# Raspberry_Pi_Grove_Base_HAT.net
KiCad netlist of a schematic drawn in EAGLE
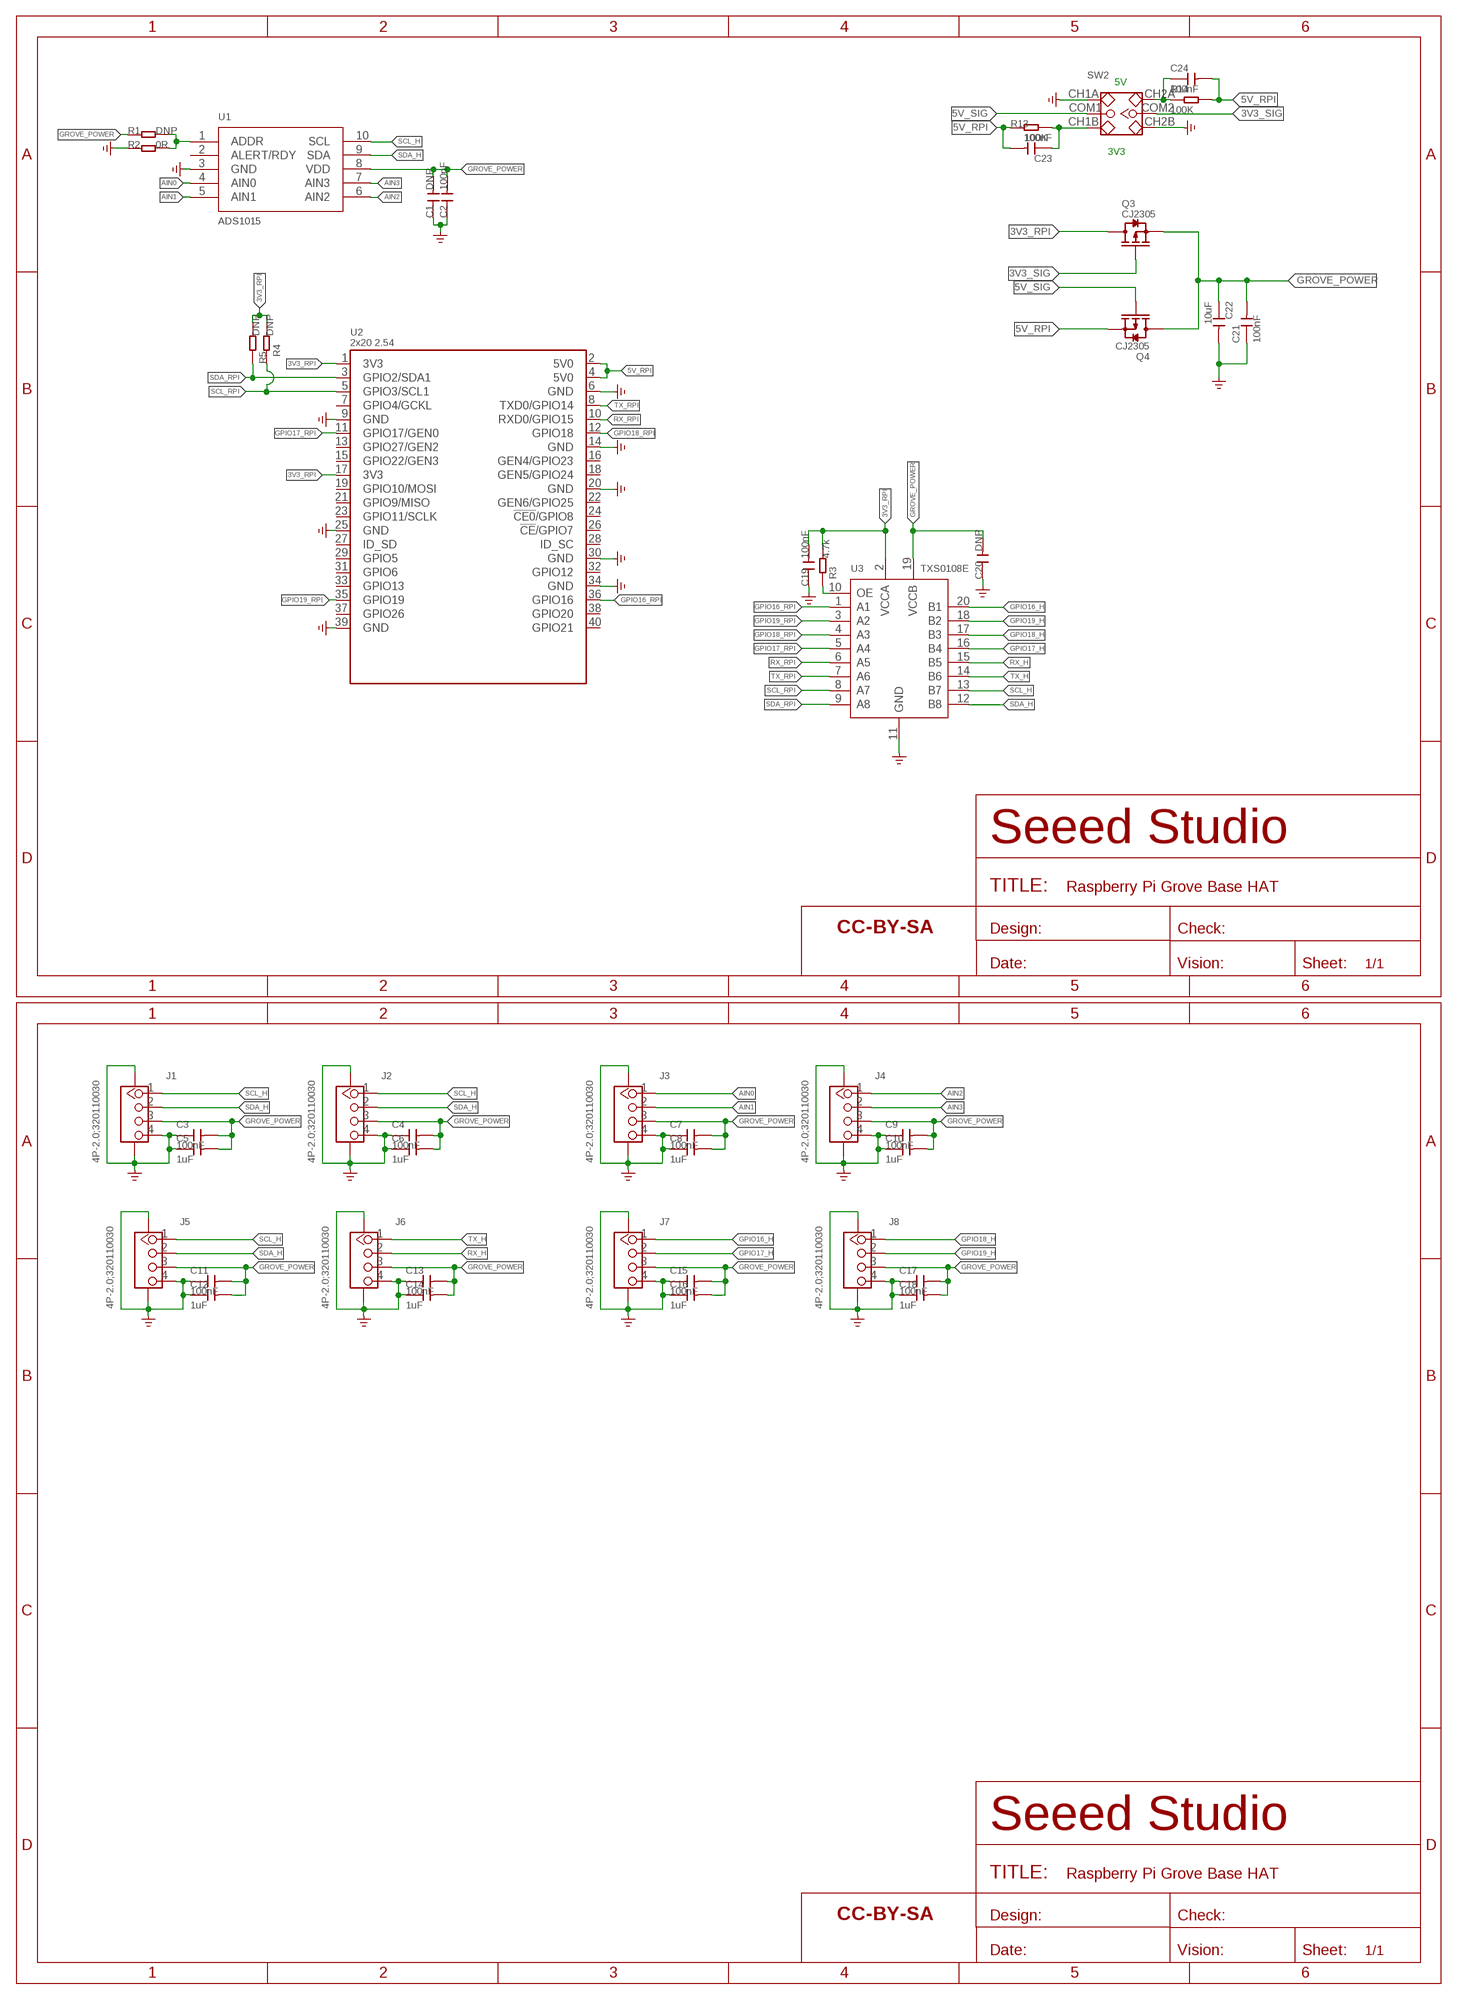
[diagram p0: schematic, sheet 1]

(export (version "E")
  (design (tool "Eeschema 10.0.6"))
  (components
    (comp (ref "C1")
      (value "DNP")
      (footprint "eagle-import:C0603")
      (libsource (lib "eagle-import") (part "CAP-0603"))
    )
    (comp (ref "C2")
      (value "100nF")
      (footprint "eagle-import:C0603")
      (libsource (lib "eagle-import") (part "CAP-0603"))
    )
    (comp (ref "C3")
      (value "100nF")
      (footprint "eagle-import:C0603")
      (libsource (lib "eagle-import") (part "CAP-0603"))
    )
    (comp (ref "C4")
      (value "100nF")
      (footprint "eagle-import:C0603")
      (libsource (lib "eagle-import") (part "CAP-0603"))
    )
    (comp (ref "C5")
      (value "1uF")
      (footprint "eagle-import:C0603")
      (libsource (lib "eagle-import") (part "CAP-0603"))
    )
    (comp (ref "C6")
      (value "1uF")
      (footprint "eagle-import:C0603")
      (libsource (lib "eagle-import") (part "CAP-0603"))
    )
    (comp (ref "C7")
      (value "100nF")
      (footprint "eagle-import:C0603")
      (libsource (lib "eagle-import") (part "CAP-0603"))
    )
    (comp (ref "C8")
      (value "1uF")
      (footprint "eagle-import:C0603")
      (libsource (lib "eagle-import") (part "CAP-0603"))
    )
    (comp (ref "C9")
      (value "100nF")
      (footprint "eagle-import:C0603")
      (libsource (lib "eagle-import") (part "CAP-0603"))
    )
    (comp (ref "C10")
      (value "1uF")
      (footprint "eagle-import:C0603")
      (libsource (lib "eagle-import") (part "CAP-0603"))
    )
    (comp (ref "C11")
      (value "100nF")
      (footprint "eagle-import:C0603")
      (libsource (lib "eagle-import") (part "CAP-0603"))
    )
    (comp (ref "C12")
      (value "1uF")
      (footprint "eagle-import:C0603")
      (libsource (lib "eagle-import") (part "CAP-0603"))
    )
    (comp (ref "C13")
      (value "100nF")
      (footprint "eagle-import:C0603")
      (libsource (lib "eagle-import") (part "CAP-0603"))
    )
    (comp (ref "C14")
      (value "1uF")
      (footprint "eagle-import:C0603")
      (libsource (lib "eagle-import") (part "CAP-0603"))
    )
    (comp (ref "C15")
      (value "100nF")
      (footprint "eagle-import:C0603")
      (libsource (lib "eagle-import") (part "CAP-0603"))
    )
    (comp (ref "C16")
      (value "1uF")
      (footprint "eagle-import:C0603")
      (libsource (lib "eagle-import") (part "CAP-0603"))
    )
    (comp (ref "C17")
      (value "100nF")
      (footprint "eagle-import:C0603")
      (libsource (lib "eagle-import") (part "CAP-0603"))
    )
    (comp (ref "C18")
      (value "1uF")
      (footprint "eagle-import:C0603")
      (libsource (lib "eagle-import") (part "CAP-0603"))
    )
    (comp (ref "C19")
      (value "100nF")
      (footprint "eagle-import:C0603")
      (libsource (lib "eagle-import") (part "CAP-0603"))
    )
    (comp (ref "C20")
      (value "DNP")
      (footprint "eagle-import:C0603")
      (libsource (lib "eagle-import") (part "CAP-0603"))
    )
    (comp (ref "C21")
      (value "100nF")
      (footprint "eagle-import:C0603")
      (libsource (lib "eagle-import") (part "CAP-0603"))
    )
    (comp (ref "C22")
      (value "10uF")
      (footprint "eagle-import:C0603")
      (libsource (lib "eagle-import") (part "CAP-0603"))
    )
    (comp (ref "C23")
      (value "100nF")
      (footprint "eagle-import:C0603")
      (libsource (lib "eagle-import") (part "CAP-0603"))
    )
    (comp (ref "C24")
      (value "100nF")
      (footprint "eagle-import:C0603")
      (libsource (lib "eagle-import") (part "CAP-0603"))
    )
    (comp (ref "FR")
      (value "SEEEDSTUDIO-OPEN-SCH-FRAME")
      (footprint "eagle-import:SEEEDSTUDIO-PCB-FRAME")
      (libsource (lib "eagle-import") (part "SEEEDSTUDIO-OPEN-SCH-FRAME"))
    )
    (comp (ref "FR1")
      (value "SEEEDSTUDIO-OPEN-SCH-FRAME")
      (footprint "eagle-import:SEEEDSTUDIO-PCB-FRAME")
      (libsource (lib "eagle-import") (part "SEEEDSTUDIO-OPEN-SCH-FRAME"))
    )
    (comp (ref "J1")
      (value "4P-2.0;320110030")
      (footprint "eagle-import:HW4-SMD-2.0")
      (libsource (lib "eagle-import") (part "GROVE-CONNECTOR-SMD'DD'"))
    )
    (comp (ref "J2")
      (value "4P-2.0;320110030")
      (footprint "eagle-import:HW4-SMD-2.0")
      (libsource (lib "eagle-import") (part "GROVE-CONNECTOR-SMD'DD'"))
    )
    (comp (ref "J3")
      (value "4P-2.0;320110030")
      (footprint "eagle-import:HW4-SMD-2.0")
      (libsource (lib "eagle-import") (part "GROVE-CONNECTOR-SMD'DD'"))
    )
    (comp (ref "J4")
      (value "4P-2.0;320110030")
      (footprint "eagle-import:HW4-SMD-2.0")
      (libsource (lib "eagle-import") (part "GROVE-CONNECTOR-SMD'DD'"))
    )
    (comp (ref "J5")
      (value "4P-2.0;320110030")
      (footprint "eagle-import:HW4-SMD-2.0")
      (libsource (lib "eagle-import") (part "GROVE-CONNECTOR-SMD'DD'"))
    )
    (comp (ref "J6")
      (value "4P-2.0;320110030")
      (footprint "eagle-import:HW4-SMD-2.0")
      (libsource (lib "eagle-import") (part "GROVE-CONNECTOR-SMD'DD'"))
    )
    (comp (ref "J7")
      (value "4P-2.0;320110030")
      (footprint "eagle-import:HW4-SMD-2.0-90D")
      (libsource (lib "eagle-import") (part "GROVE-CONNECTOR-SMD'90D'"))
    )
    (comp (ref "J8")
      (value "4P-2.0;320110030")
      (footprint "eagle-import:HW4-SMD-2.0-90D")
      (libsource (lib "eagle-import") (part "GROVE-CONNECTOR-SMD'90D'"))
    )
    (comp (ref "Q3")
      (value "CJ2305")
      (footprint "eagle-import:SOT-23")
      (libsource (lib "eagle-import") (part "MOSFET-P'SI2323CDS/SI2305DS{lt}BR{gt}'"))
    )
    (comp (ref "Q4")
      (value "CJ2305")
      (footprint "eagle-import:SOT-23")
      (libsource (lib "eagle-import") (part "MOSFET-P'SI2323CDS/SI2305DS{lt}BR{gt}'"))
    )
    (comp (ref "R1")
      (value "DNP")
      (footprint "eagle-import:R0603")
      (libsource (lib "eagle-import") (part "RES-0603"))
    )
    (comp (ref "R2")
      (value "0R")
      (footprint "eagle-import:R0603")
      (libsource (lib "eagle-import") (part "RES-0603"))
    )
    (comp (ref "R3")
      (value "4.7k")
      (footprint "eagle-import:R0603")
      (libsource (lib "eagle-import") (part "RES-0603"))
    )
    (comp (ref "R4")
      (value "DNP")
      (footprint "eagle-import:R0603")
      (libsource (lib "eagle-import") (part "RES-0603"))
    )
    (comp (ref "R5")
      (value "DNP")
      (footprint "eagle-import:R0603")
      (libsource (lib "eagle-import") (part "RES-0603"))
    )
    (comp (ref "R13")
      (value "100K")
      (footprint "eagle-import:R0603")
      (libsource (lib "eagle-import") (part "RES-0603"))
    )
    (comp (ref "R14")
      (value "100K")
      (footprint "eagle-import:R0603")
      (libsource (lib "eagle-import") (part "RES-0603"))
    )
    (comp (ref "SW2")
      (value "SWITCH-2CH-6P-2.54")
      (footprint "eagle-import:6P-SMD-2CH-2.54-3.5X7.2")
      (libsource (lib "eagle-import") (part "SWITCH-2CH-6P-SMD"))
    )
    (comp (ref "U1")
      (value "ADS1015")
      (footprint "eagle-import:SSOP10-0.5-3X3MM")
      (fields (field (name "MPN") "ADS1015IDGST-ADC-兼容1.8V-3.3V"))
      (libsource (lib "eagle-import") (part "CONVERTER-ADS1015IDGST-ADC"))
    )
    (comp (ref "U2")
      (value "2x20 2.54")
      (footprint "eagle-import:RASPI_BOARD_B+HAT_DF_CF")
      (libsource (lib "eagle-import") (part "RPI-ZERO-65X56"))
    )
    (comp (ref "U3")
      (value "TXS0108E")
      (footprint "eagle-import:TSSOP20-0.65-6.5X4.4MM")
      (libsource (lib "eagle-import") (part "LOGIC-TXS0108EPWR"))
    )
  )
  (nets
    (net (code "1") (name "3V3_RPI") (class "Default")
      (node (ref "C19") (pin "2") (pinfunction "2_2") (pintype "passive"))
      (node (ref "Q3") (pin "3") (pinfunction "D_3") (pintype "passive"))
      (node (ref "R3") (pin "2") (pinfunction "2_2") (pintype "passive"))
      (node (ref "R4") (pin "2") (pinfunction "2_2") (pintype "passive"))
      (node (ref "R5") (pin "2") (pinfunction "2_2") (pintype "passive"))
      (node (ref "U2") (pin "1") (pinfunction "3V3_1") (pintype "power_in"))
      (node (ref "U2") (pin "17") (pinfunction "3V3_17") (pintype "power_in"))
      (node (ref "U3") (pin "2") (pinfunction "VCCA_2") (pintype "bidirectional"))
    )
    (net (code "2") (name "3V3_SIG") (class "Default")
      (node (ref "Q3") (pin "1") (pinfunction "G_1") (pintype "passive"))
      (node (ref "SW2") (pin "COM2") (pinfunction "COM2_COM2") (pintype "bidirectional"))
    )
    (net (code "3") (name "5V_RPI") (class "Default")
      (node (ref "C23") (pin "2") (pinfunction "2_2") (pintype "passive"))
      (node (ref "C24") (pin "2") (pinfunction "2_2") (pintype "passive"))
      (node (ref "Q4") (pin "2") (pinfunction "S_2") (pintype "passive"))
      (node (ref "R13") (pin "1") (pinfunction "1_1") (pintype "passive"))
      (node (ref "R14") (pin "2") (pinfunction "2_2") (pintype "passive"))
      (node (ref "U2") (pin "2") (pinfunction "5V0_2") (pintype "power_in"))
      (node (ref "U2") (pin "4") (pinfunction "5V0_4") (pintype "power_in"))
    )
    (net (code "4") (name "5V_SIG") (class "Default")
      (node (ref "Q4") (pin "1") (pinfunction "G_1") (pintype "passive"))
      (node (ref "SW2") (pin "COM1") (pinfunction "COM1_COM1") (pintype "bidirectional"))
    )
    (net (code "5") (name "AIN0") (class "Default")
      (node (ref "J3") (pin "1") (pinfunction "1_1") (pintype "bidirectional"))
      (node (ref "U1") (pin "4") (pinfunction "AIN0_4") (pintype "bidirectional"))
    )
    (net (code "6") (name "AIN1") (class "Default")
      (node (ref "J3") (pin "2") (pinfunction "2_2") (pintype "bidirectional"))
      (node (ref "U1") (pin "5") (pinfunction "AIN1_5") (pintype "bidirectional"))
    )
    (net (code "7") (name "AIN2") (class "Default")
      (node (ref "J4") (pin "1") (pinfunction "1_1") (pintype "bidirectional"))
      (node (ref "U1") (pin "6") (pinfunction "AIN2_6") (pintype "bidirectional"))
    )
    (net (code "8") (name "AIN3") (class "Default")
      (node (ref "J4") (pin "2") (pinfunction "2_2") (pintype "bidirectional"))
      (node (ref "U1") (pin "7") (pinfunction "AIN3_7") (pintype "bidirectional"))
    )
    (net (code "9") (name "GND_POWER") (class "Default")
      (node (ref "C1") (pin "1") (pinfunction "1_1") (pintype "passive"))
      (node (ref "C10") (pin "1") (pinfunction "1_1") (pintype "passive"))
      (node (ref "C11") (pin "1") (pinfunction "1_1") (pintype "passive"))
      (node (ref "C12") (pin "1") (pinfunction "1_1") (pintype "passive"))
      (node (ref "C13") (pin "1") (pinfunction "1_1") (pintype "passive"))
      (node (ref "C14") (pin "1") (pinfunction "1_1") (pintype "passive"))
      (node (ref "C15") (pin "1") (pinfunction "1_1") (pintype "passive"))
      (node (ref "C16") (pin "1") (pinfunction "1_1") (pintype "passive"))
      (node (ref "C17") (pin "1") (pinfunction "1_1") (pintype "passive"))
      (node (ref "C18") (pin "1") (pinfunction "1_1") (pintype "passive"))
      (node (ref "C19") (pin "1") (pinfunction "1_1") (pintype "passive"))
      (node (ref "C2") (pin "1") (pinfunction "1_1") (pintype "passive"))
      (node (ref "C20") (pin "1") (pinfunction "1_1") (pintype "passive"))
      (node (ref "C21") (pin "1") (pinfunction "1_1") (pintype "passive"))
      (node (ref "C22") (pin "2") (pinfunction "2_2") (pintype "passive"))
      (node (ref "C3") (pin "1") (pinfunction "1_1") (pintype "passive"))
      (node (ref "C4") (pin "1") (pinfunction "1_1") (pintype "passive"))
      (node (ref "C5") (pin "1") (pinfunction "1_1") (pintype "passive"))
      (node (ref "C6") (pin "1") (pinfunction "1_1") (pintype "passive"))
      (node (ref "C7") (pin "1") (pinfunction "1_1") (pintype "passive"))
      (node (ref "C8") (pin "1") (pinfunction "1_1") (pintype "passive"))
      (node (ref "C9") (pin "1") (pinfunction "1_1") (pintype "passive"))
      (node (ref "J1") (pin "4") (pinfunction "4_4") (pintype "bidirectional"))
      (node (ref "J1") (pin "SS1") (pinfunction "SS1_SS1") (pintype "bidirectional"))
      (node (ref "J1") (pin "SS2") (pinfunction "SS2_SS2") (pintype "bidirectional"))
      (node (ref "J2") (pin "4") (pinfunction "4_4") (pintype "bidirectional"))
      (node (ref "J2") (pin "SS1") (pinfunction "SS1_SS1") (pintype "bidirectional"))
      (node (ref "J2") (pin "SS2") (pinfunction "SS2_SS2") (pintype "bidirectional"))
      (node (ref "J3") (pin "4") (pinfunction "4_4") (pintype "bidirectional"))
      (node (ref "J3") (pin "SS1") (pinfunction "SS1_SS1") (pintype "bidirectional"))
      (node (ref "J3") (pin "SS2") (pinfunction "SS2_SS2") (pintype "bidirectional"))
      (node (ref "J4") (pin "4") (pinfunction "4_4") (pintype "bidirectional"))
      (node (ref "J4") (pin "SS1") (pinfunction "SS1_SS1") (pintype "bidirectional"))
      (node (ref "J4") (pin "SS2") (pinfunction "SS2_SS2") (pintype "bidirectional"))
      (node (ref "J5") (pin "4") (pinfunction "4_4") (pintype "bidirectional"))
      (node (ref "J5") (pin "SS1") (pinfunction "SS1_SS1") (pintype "bidirectional"))
      (node (ref "J5") (pin "SS2") (pinfunction "SS2_SS2") (pintype "bidirectional"))
      (node (ref "J6") (pin "4") (pinfunction "4_4") (pintype "bidirectional"))
      (node (ref "J6") (pin "SS1") (pinfunction "SS1_SS1") (pintype "bidirectional"))
      (node (ref "J6") (pin "SS2") (pinfunction "SS2_SS2") (pintype "bidirectional"))
      (node (ref "J7") (pin "4") (pinfunction "4_4") (pintype "bidirectional"))
      (node (ref "J7") (pin "SS1") (pinfunction "SS1_SS1") (pintype "bidirectional"))
      (node (ref "J7") (pin "SS2") (pinfunction "SS2_SS2") (pintype "bidirectional"))
      (node (ref "J8") (pin "4") (pinfunction "4_4") (pintype "bidirectional"))
      (node (ref "J8") (pin "SS1") (pinfunction "SS1_SS1") (pintype "bidirectional"))
      (node (ref "J8") (pin "SS2") (pinfunction "SS2_SS2") (pintype "bidirectional"))
      (node (ref "R2") (pin "1") (pinfunction "1_1") (pintype "passive"))
      (node (ref "SW2") (pin "CH1A") (pinfunction "CH1A_CH1A") (pintype "bidirectional"))
      (node (ref "SW2") (pin "CH2B") (pinfunction "CH2B_CH2B") (pintype "bidirectional"))
      (node (ref "U1") (pin "3") (pinfunction "GND_3") (pintype "bidirectional"))
      (node (ref "U2") (pin "14") (pinfunction "GND_14") (pintype "power_in"))
      (node (ref "U2") (pin "20") (pinfunction "GND_20") (pintype "power_in"))
      (node (ref "U2") (pin "25") (pinfunction "GND_25") (pintype "power_in"))
      (node (ref "U2") (pin "30") (pinfunction "GND_30") (pintype "power_in"))
      (node (ref "U2") (pin "34") (pinfunction "GND_34") (pintype "power_in"))
      (node (ref "U2") (pin "39") (pinfunction "GND_39") (pintype "power_in"))
      (node (ref "U2") (pin "6") (pinfunction "GND_6") (pintype "power_in"))
      (node (ref "U2") (pin "9") (pinfunction "GND_9") (pintype "power_in"))
      (node (ref "U3") (pin "11") (pinfunction "GND_11") (pintype "bidirectional"))
    )
    (net (code "10") (name "GPIO16_H") (class "Default")
      (node (ref "J7") (pin "1") (pinfunction "1_1") (pintype "bidirectional"))
      (node (ref "U3") (pin "20") (pinfunction "B1_20") (pintype "bidirectional"))
    )
    (net (code "11") (name "GPIO16_RPI") (class "Default")
      (node (ref "U2") (pin "36") (pinfunction "GPIO16_36") (pintype "bidirectional"))
      (node (ref "U3") (pin "1") (pinfunction "A1_1") (pintype "bidirectional"))
    )
    (net (code "12") (name "GPIO17_H") (class "Default")
      (node (ref "J7") (pin "2") (pinfunction "2_2") (pintype "bidirectional"))
      (node (ref "U3") (pin "16") (pinfunction "B4_16") (pintype "bidirectional"))
    )
    (net (code "13") (name "GPIO17_RPI") (class "Default")
      (node (ref "U2") (pin "11") (pinfunction "GPIO17/GEN0_11") (pintype "bidirectional"))
      (node (ref "U3") (pin "5") (pinfunction "A4_5") (pintype "bidirectional"))
    )
    (net (code "14") (name "GPIO18_H") (class "Default")
      (node (ref "J8") (pin "1") (pinfunction "1_1") (pintype "bidirectional"))
      (node (ref "U3") (pin "17") (pinfunction "B3_17") (pintype "bidirectional"))
    )
    (net (code "15") (name "GPIO18_RPI") (class "Default")
      (node (ref "U2") (pin "12") (pinfunction "GPIO18_12") (pintype "bidirectional"))
      (node (ref "U3") (pin "4") (pinfunction "A3_4") (pintype "bidirectional"))
    )
    (net (code "16") (name "GPIO19_H") (class "Default")
      (node (ref "J8") (pin "2") (pinfunction "2_2") (pintype "bidirectional"))
      (node (ref "U3") (pin "18") (pinfunction "B2_18") (pintype "bidirectional"))
    )
    (net (code "17") (name "GPIO19_RPI") (class "Default")
      (node (ref "U2") (pin "35") (pinfunction "GPIO19_35") (pintype "bidirectional"))
      (node (ref "U3") (pin "3") (pinfunction "A2_3") (pintype "bidirectional"))
    )
    (net (code "18") (name "GROVE_POWER") (class "Default")
      (node (ref "C1") (pin "2") (pinfunction "2_2") (pintype "passive"))
      (node (ref "C10") (pin "2") (pinfunction "2_2") (pintype "passive"))
      (node (ref "C11") (pin "2") (pinfunction "2_2") (pintype "passive"))
      (node (ref "C12") (pin "2") (pinfunction "2_2") (pintype "passive"))
      (node (ref "C13") (pin "2") (pinfunction "2_2") (pintype "passive"))
      (node (ref "C14") (pin "2") (pinfunction "2_2") (pintype "passive"))
      (node (ref "C15") (pin "2") (pinfunction "2_2") (pintype "passive"))
      (node (ref "C16") (pin "2") (pinfunction "2_2") (pintype "passive"))
      (node (ref "C17") (pin "2") (pinfunction "2_2") (pintype "passive"))
      (node (ref "C18") (pin "2") (pinfunction "2_2") (pintype "passive"))
      (node (ref "C2") (pin "2") (pinfunction "2_2") (pintype "passive"))
      (node (ref "C20") (pin "2") (pinfunction "2_2") (pintype "passive"))
      (node (ref "C21") (pin "2") (pinfunction "2_2") (pintype "passive"))
      (node (ref "C22") (pin "1") (pinfunction "1_1") (pintype "passive"))
      (node (ref "C3") (pin "2") (pinfunction "2_2") (pintype "passive"))
      (node (ref "C4") (pin "2") (pinfunction "2_2") (pintype "passive"))
      (node (ref "C5") (pin "2") (pinfunction "2_2") (pintype "passive"))
      (node (ref "C6") (pin "2") (pinfunction "2_2") (pintype "passive"))
      (node (ref "C7") (pin "2") (pinfunction "2_2") (pintype "passive"))
      (node (ref "C8") (pin "2") (pinfunction "2_2") (pintype "passive"))
      (node (ref "C9") (pin "2") (pinfunction "2_2") (pintype "passive"))
      (node (ref "J1") (pin "3") (pinfunction "3_3") (pintype "bidirectional"))
      (node (ref "J2") (pin "3") (pinfunction "3_3") (pintype "bidirectional"))
      (node (ref "J3") (pin "3") (pinfunction "3_3") (pintype "bidirectional"))
      (node (ref "J4") (pin "3") (pinfunction "3_3") (pintype "bidirectional"))
      (node (ref "J5") (pin "3") (pinfunction "3_3") (pintype "bidirectional"))
      (node (ref "J6") (pin "3") (pinfunction "3_3") (pintype "bidirectional"))
      (node (ref "J7") (pin "3") (pinfunction "3_3") (pintype "bidirectional"))
      (node (ref "J8") (pin "3") (pinfunction "3_3") (pintype "bidirectional"))
      (node (ref "Q3") (pin "2") (pinfunction "S_2") (pintype "passive"))
      (node (ref "Q4") (pin "3") (pinfunction "D_3") (pintype "passive"))
      (node (ref "R1") (pin "1") (pinfunction "1_1") (pintype "passive"))
      (node (ref "U1") (pin "8") (pinfunction "VDD_8") (pintype "bidirectional"))
      (node (ref "U3") (pin "19") (pinfunction "VCCB_19") (pintype "bidirectional"))
    )
    (net (code "19") (name "Net-(C23-Pad1)") (class "Default")
      (node (ref "C23") (pin "1") (pinfunction "1_1") (pintype "passive"))
      (node (ref "R13") (pin "2") (pinfunction "2_2") (pintype "passive"))
      (node (ref "SW2") (pin "CH1B") (pinfunction "CH1B_CH1B") (pintype "bidirectional"))
    )
    (net (code "20") (name "Net-(C24-Pad1)") (class "Default")
      (node (ref "C24") (pin "1") (pinfunction "1_1") (pintype "passive"))
      (node (ref "R14") (pin "1") (pinfunction "1_1") (pintype "passive"))
      (node (ref "SW2") (pin "CH2A") (pinfunction "CH2A_CH2A") (pintype "bidirectional"))
    )
    (net (code "21") (name "Net-(U1-ADDR)") (class "Default")
      (node (ref "R1") (pin "2") (pinfunction "2_2") (pintype "passive"))
      (node (ref "R2") (pin "2") (pinfunction "2_2") (pintype "passive"))
      (node (ref "U1") (pin "1") (pinfunction "ADDR_1") (pintype "bidirectional"))
    )
    (net (code "22") (name "Net-(U3-OE)") (class "Default")
      (node (ref "R3") (pin "1") (pinfunction "1_1") (pintype "passive"))
      (node (ref "U3") (pin "10") (pinfunction "OE_10") (pintype "bidirectional"))
    )
    (net (code "23") (name "RX_H") (class "Default")
      (node (ref "J6") (pin "2") (pinfunction "2_2") (pintype "bidirectional"))
      (node (ref "U3") (pin "15") (pinfunction "B5_15") (pintype "bidirectional"))
    )
    (net (code "24") (name "RX_RPI") (class "Default")
      (node (ref "U2") (pin "10") (pinfunction "RXD0/GPIO15_10") (pintype "bidirectional"))
      (node (ref "U3") (pin "6") (pinfunction "A5_6") (pintype "bidirectional"))
    )
    (net (code "25") (name "SCL_H") (class "Default")
      (node (ref "J1") (pin "1") (pinfunction "1_1") (pintype "bidirectional"))
      (node (ref "J2") (pin "1") (pinfunction "1_1") (pintype "bidirectional"))
      (node (ref "J5") (pin "1") (pinfunction "1_1") (pintype "bidirectional"))
      (node (ref "U1") (pin "10") (pinfunction "SCL_10") (pintype "bidirectional"))
      (node (ref "U3") (pin "13") (pinfunction "B7_13") (pintype "bidirectional"))
    )
    (net (code "26") (name "SCL_RPI") (class "Default")
      (node (ref "R4") (pin "1") (pinfunction "1_1") (pintype "passive"))
      (node (ref "U2") (pin "5") (pinfunction "GPIO3/SCL1_5") (pintype "bidirectional"))
      (node (ref "U3") (pin "8") (pinfunction "A7_8") (pintype "bidirectional"))
    )
    (net (code "27") (name "SDA_H") (class "Default")
      (node (ref "J1") (pin "2") (pinfunction "2_2") (pintype "bidirectional"))
      (node (ref "J2") (pin "2") (pinfunction "2_2") (pintype "bidirectional"))
      (node (ref "J5") (pin "2") (pinfunction "2_2") (pintype "bidirectional"))
      (node (ref "U1") (pin "9") (pinfunction "SDA_9") (pintype "bidirectional"))
      (node (ref "U3") (pin "12") (pinfunction "B8_12") (pintype "bidirectional"))
    )
    (net (code "28") (name "SDA_RPI") (class "Default")
      (node (ref "R5") (pin "1") (pinfunction "1_1") (pintype "passive"))
      (node (ref "U2") (pin "3") (pinfunction "GPIO2/SDA1_3") (pintype "bidirectional"))
      (node (ref "U3") (pin "9") (pinfunction "A8_9") (pintype "bidirectional"))
    )
    (net (code "29") (name "TX_H") (class "Default")
      (node (ref "J6") (pin "1") (pinfunction "1_1") (pintype "bidirectional"))
      (node (ref "U3") (pin "14") (pinfunction "B6_14") (pintype "bidirectional"))
    )
    (net (code "30") (name "TX_RPI") (class "Default")
      (node (ref "U2") (pin "8") (pinfunction "TXD0/GPIO14_8") (pintype "bidirectional"))
      (node (ref "U3") (pin "7") (pinfunction "A6_7") (pintype "bidirectional"))
    )
    (net (code "31") (name "unconnected-(U1-ALERT{slash}RDY-Pad2)") (class "Default")
      (node (ref "U1") (pin "2") (pinfunction "ALERT/RDY_2") (pintype "bidirectional"))
    )
    (net (code "32") (name "unconnected-(U2-GEN4{slash}GPIO23-Pad16)") (class "Default")
      (node (ref "U2") (pin "16") (pinfunction "GEN4/GPIO23_16") (pintype "bidirectional"))
    )
    (net (code "33") (name "unconnected-(U2-GEN5{slash}GPIO24-Pad18)") (class "Default")
      (node (ref "U2") (pin "18") (pinfunction "GEN5/GPIO24_18") (pintype "bidirectional"))
    )
    (net (code "34") (name "unconnected-(U2-GEN6{slash}GPIO25-Pad22)") (class "Default")
      (node (ref "U2") (pin "22") (pinfunction "GEN6/GPIO25_22") (pintype "bidirectional"))
    )
    (net (code "35") (name "unconnected-(U2-GPIO4{slash}GCKL-Pad7)") (class "Default")
      (node (ref "U2") (pin "7") (pinfunction "GPIO4/GCKL_7") (pintype "bidirectional"))
    )
    (net (code "36") (name "unconnected-(U2-GPIO5-Pad29)") (class "Default")
      (node (ref "U2") (pin "29") (pinfunction "GPIO5_29") (pintype "bidirectional"))
    )
    (net (code "37") (name "unconnected-(U2-GPIO6-Pad31)") (class "Default")
      (node (ref "U2") (pin "31") (pinfunction "GPIO6_31") (pintype "bidirectional"))
    )
    (net (code "38") (name "unconnected-(U2-GPIO9{slash}MISO-Pad21)") (class "Default")
      (node (ref "U2") (pin "21") (pinfunction "GPIO9/MISO_21") (pintype "bidirectional"))
    )
    (net (code "39") (name "unconnected-(U2-GPIO10{slash}MOSI-Pad19)") (class "Default")
      (node (ref "U2") (pin "19") (pinfunction "GPIO10/MOSI_19") (pintype "bidirectional"))
    )
    (net (code "40") (name "unconnected-(U2-GPIO11{slash}SCLK-Pad23)") (class "Default")
      (node (ref "U2") (pin "23") (pinfunction "GPIO11/SCLK_23") (pintype "bidirectional"))
    )
    (net (code "41") (name "unconnected-(U2-GPIO12-Pad32)") (class "Default")
      (node (ref "U2") (pin "32") (pinfunction "GPIO12_32") (pintype "bidirectional"))
    )
    (net (code "42") (name "unconnected-(U2-GPIO13-Pad33)") (class "Default")
      (node (ref "U2") (pin "33") (pinfunction "GPIO13_33") (pintype "bidirectional"))
    )
    (net (code "43") (name "unconnected-(U2-GPIO20-Pad38)") (class "Default")
      (node (ref "U2") (pin "38") (pinfunction "GPIO20_38") (pintype "bidirectional"))
    )
    (net (code "44") (name "unconnected-(U2-GPIO21-Pad40)") (class "Default")
      (node (ref "U2") (pin "40") (pinfunction "GPIO21_40") (pintype "bidirectional"))
    )
    (net (code "45") (name "unconnected-(U2-GPIO22{slash}GEN3-Pad15)") (class "Default")
      (node (ref "U2") (pin "15") (pinfunction "GPIO22/GEN3_15") (pintype "bidirectional"))
    )
    (net (code "46") (name "unconnected-(U2-GPIO26-Pad37)") (class "Default")
      (node (ref "U2") (pin "37") (pinfunction "GPIO26_37") (pintype "bidirectional"))
    )
    (net (code "47") (name "unconnected-(U2-GPIO27{slash}GEN2-Pad13)") (class "Default")
      (node (ref "U2") (pin "13") (pinfunction "GPIO27/GEN2_13") (pintype "bidirectional"))
    )
    (net (code "48") (name "unconnected-(U2-ID_SC-Pad28)") (class "Default")
      (node (ref "U2") (pin "28") (pinfunction "ID_SC_28") (pintype "bidirectional"))
    )
    (net (code "49") (name "unconnected-(U2-ID_SD-Pad27)") (class "Default")
      (node (ref "U2") (pin "27") (pinfunction "ID_SD_27") (pintype "bidirectional"))
    )
    (net (code "50") (name "unconnected-(U2-~{CE0}{slash}GPIO8-Pad24)") (class "Default")
      (node (ref "U2") (pin "24") (pinfunction "~{CE0}/GPIO8_24") (pintype "bidirectional"))
    )
    (net (code "51") (name "unconnected-(U2-~{CE}{slash}GPIO7-Pad26)") (class "Default")
      (node (ref "U2") (pin "26") (pinfunction "~{CE}/GPIO7_26") (pintype "bidirectional"))
    )
  )
)
